# AM1027_POTS_REV01.net
KiCad netlist of a schematic drawn in EAGLE
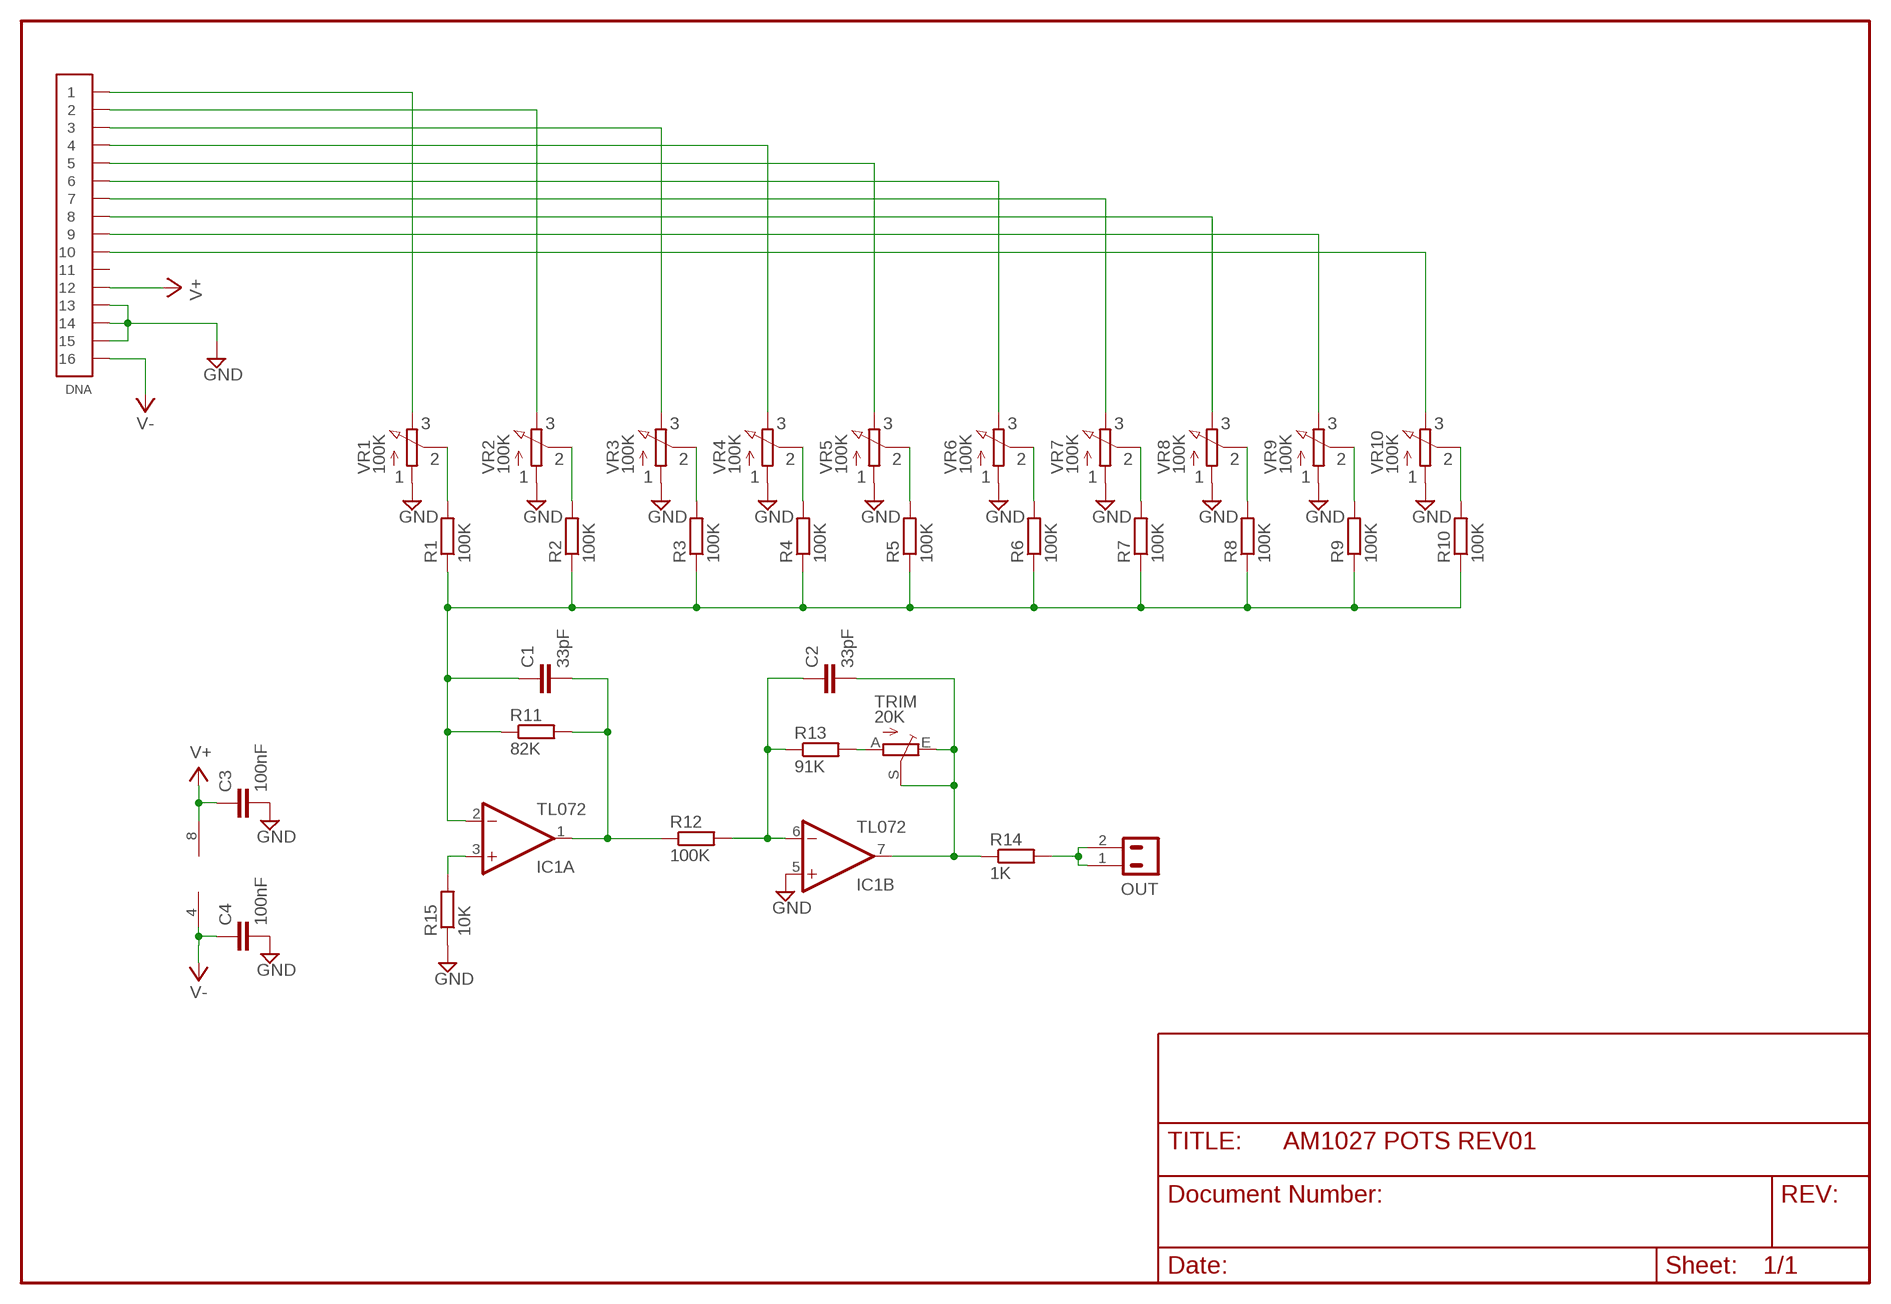
[diagram p0: schematic, sheet 1]

(export (version "E")
  (design (tool "Eeschema 10.0.6"))
  (components
    (comp (ref "C1")
      (value "33pF")
      (footprint "eagle-import:C050-025X075AM")
      (libsource (lib "eagle-import") (part "C-EU050-025X075AM"))
    )
    (comp (ref "C2")
      (value "33pF")
      (footprint "eagle-import:C050-025X075AM")
      (libsource (lib "eagle-import") (part "C-EU050-025X075AM"))
    )
    (comp (ref "C3")
      (value "100nF")
      (footprint "eagle-import:C050-025X075AM")
      (libsource (lib "eagle-import") (part "C-EU050-025X075AM"))
    )
    (comp (ref "C4")
      (value "100nF")
      (footprint "eagle-import:C050-025X075AM")
      (libsource (lib "eagle-import") (part "C-EU050-025X075AM"))
    )
    (comp (ref "DNA")
      (value "AMPWR16PIN")
      (footprint "eagle-import:AMPWR16")
      (libsource (lib "eagle-import") (part "AMPWR16PIN"))
    )
    (comp (ref "IC1")
      (value "TL072")
      (footprint "eagle-import:DIL08AM")
      (libsource (lib "eagle-import") (part "TL072"))
    )
    (comp (ref "OUT")
      (value "MA02-AM")
      (footprint "eagle-import:MA02-AM")
      (libsource (lib "eagle-import") (part "MA02-AM"))
    )
    (comp (ref "R1")
      (value "100K")
      (footprint "eagle-import:0207_10_AM")
      (libsource (lib "eagle-import") (part "R-EU_0207/10-AM"))
    )
    (comp (ref "R2")
      (value "100K")
      (footprint "eagle-import:0207_10_AM")
      (libsource (lib "eagle-import") (part "R-EU_0207/10-AM"))
    )
    (comp (ref "R3")
      (value "100K")
      (footprint "eagle-import:0207_10_AM")
      (libsource (lib "eagle-import") (part "R-EU_0207/10-AM"))
    )
    (comp (ref "R4")
      (value "100K")
      (footprint "eagle-import:0207_10_AM")
      (libsource (lib "eagle-import") (part "R-EU_0207/10-AM"))
    )
    (comp (ref "R5")
      (value "100K")
      (footprint "eagle-import:0207_10_AM")
      (libsource (lib "eagle-import") (part "R-EU_0207/10-AM"))
    )
    (comp (ref "R6")
      (value "100K")
      (footprint "eagle-import:0207_10_AM")
      (libsource (lib "eagle-import") (part "R-EU_0207/10-AM"))
    )
    (comp (ref "R7")
      (value "100K")
      (footprint "eagle-import:0207_10_AM")
      (libsource (lib "eagle-import") (part "R-EU_0207/10-AM"))
    )
    (comp (ref "R8")
      (value "100K")
      (footprint "eagle-import:0207_10_AM")
      (libsource (lib "eagle-import") (part "R-EU_0207/10-AM"))
    )
    (comp (ref "R9")
      (value "100K")
      (footprint "eagle-import:0207_10_AM")
      (libsource (lib "eagle-import") (part "R-EU_0207/10-AM"))
    )
    (comp (ref "R10")
      (value "100K")
      (footprint "eagle-import:0207_10_AM")
      (libsource (lib "eagle-import") (part "R-EU_0207/10-AM"))
    )
    (comp (ref "R11")
      (value "82K")
      (footprint "eagle-import:0207_10_AM")
      (libsource (lib "eagle-import") (part "R-EU_0207/10-AM"))
    )
    (comp (ref "R12")
      (value "100K")
      (footprint "eagle-import:0207_10_AM")
      (libsource (lib "eagle-import") (part "R-EU_0207/10-AM"))
    )
    (comp (ref "R13")
      (value "91K")
      (footprint "eagle-import:0207_10_AM")
      (libsource (lib "eagle-import") (part "R-EU_0207/10-AM"))
    )
    (comp (ref "R14")
      (value "1K")
      (footprint "eagle-import:0207_10_AM")
      (libsource (lib "eagle-import") (part "R-EU_0207/10-AM"))
    )
    (comp (ref "R15")
      (value "10K")
      (footprint "eagle-import:0207_10_AM")
      (libsource (lib "eagle-import") (part "R-EU_0207/10-AM"))
    )
    (comp (ref "TRIM")
      (value "20K")
      (footprint "eagle-import:S64W-AM")
      (libsource (lib "eagle-import") (part "TRIM_EU-S64W"))
    )
    (comp (ref "VR1")
      (value "100K")
      (footprint "eagle-import:SPECTROL148")
      (libsource (lib "eagle-import") (part "SPECTROL148"))
    )
    (comp (ref "VR2")
      (value "100K")
      (footprint "eagle-import:SPECTROL148")
      (libsource (lib "eagle-import") (part "SPECTROL148"))
    )
    (comp (ref "VR3")
      (value "100K")
      (footprint "eagle-import:SPECTROL148")
      (libsource (lib "eagle-import") (part "SPECTROL148"))
    )
    (comp (ref "VR4")
      (value "100K")
      (footprint "eagle-import:SPECTROL148")
      (libsource (lib "eagle-import") (part "SPECTROL148"))
    )
    (comp (ref "VR5")
      (value "100K")
      (footprint "eagle-import:SPECTROL148")
      (libsource (lib "eagle-import") (part "SPECTROL148"))
    )
    (comp (ref "VR6")
      (value "100K")
      (footprint "eagle-import:SPECTROL148")
      (libsource (lib "eagle-import") (part "SPECTROL148"))
    )
    (comp (ref "VR7")
      (value "100K")
      (footprint "eagle-import:SPECTROL148")
      (libsource (lib "eagle-import") (part "SPECTROL148"))
    )
    (comp (ref "VR8")
      (value "100K")
      (footprint "eagle-import:SPECTROL148")
      (libsource (lib "eagle-import") (part "SPECTROL148"))
    )
    (comp (ref "VR9")
      (value "100K")
      (footprint "eagle-import:SPECTROL148")
      (libsource (lib "eagle-import") (part "SPECTROL148"))
    )
    (comp (ref "VR10")
      (value "100K")
      (footprint "eagle-import:SPECTROL148")
      (libsource (lib "eagle-import") (part "SPECTROL148"))
    )
  )
  (nets
    (net (code "1") (name "GND") (class "Default")
      (node (ref "C3") (pin "P$4") (pinfunction "2_P$4") (pintype "passive"))
      (node (ref "C4") (pin "P$4") (pinfunction "2_P$4") (pintype "passive"))
      (node (ref "DNA") (pin "13") (pinfunction "13_13") (pintype "bidirectional"))
      (node (ref "DNA") (pin "14") (pinfunction "14_14") (pintype "bidirectional"))
      (node (ref "DNA") (pin "15") (pinfunction "15_15") (pintype "bidirectional"))
      (node (ref "IC1") (pin "5") (pinfunction "+IN_5") (pintype "input"))
      (node (ref "R15") (pin "P$1") (pinfunction "1_P$1") (pintype "passive"))
      (node (ref "VR1") (pin "P$1") (pinfunction "A_P$1") (pintype "passive"))
      (node (ref "VR10") (pin "P$1") (pinfunction "A_P$1") (pintype "passive"))
      (node (ref "VR2") (pin "P$1") (pinfunction "A_P$1") (pintype "passive"))
      (node (ref "VR3") (pin "P$1") (pinfunction "A_P$1") (pintype "passive"))
      (node (ref "VR4") (pin "P$1") (pinfunction "A_P$1") (pintype "passive"))
      (node (ref "VR5") (pin "P$1") (pinfunction "A_P$1") (pintype "passive"))
      (node (ref "VR6") (pin "P$1") (pinfunction "A_P$1") (pintype "passive"))
      (node (ref "VR7") (pin "P$1") (pinfunction "A_P$1") (pintype "passive"))
      (node (ref "VR8") (pin "P$1") (pinfunction "A_P$1") (pintype "passive"))
      (node (ref "VR9") (pin "P$1") (pinfunction "A_P$1") (pintype "passive"))
    )
    (net (code "2") (name "Net-(C1-1)") (class "Default")
      (node (ref "C1") (pin "P$3") (pinfunction "1_P$3") (pintype "passive"))
      (node (ref "IC1") (pin "2") (pinfunction "-IN_2") (pintype "input"))
      (node (ref "R1") (pin "P$1") (pinfunction "1_P$1") (pintype "passive"))
      (node (ref "R10") (pin "P$1") (pinfunction "1_P$1") (pintype "passive"))
      (node (ref "R11") (pin "P$1") (pinfunction "1_P$1") (pintype "passive"))
      (node (ref "R2") (pin "P$1") (pinfunction "1_P$1") (pintype "passive"))
      (node (ref "R3") (pin "P$1") (pinfunction "1_P$1") (pintype "passive"))
      (node (ref "R4") (pin "P$1") (pinfunction "1_P$1") (pintype "passive"))
      (node (ref "R5") (pin "P$1") (pinfunction "1_P$1") (pintype "passive"))
      (node (ref "R6") (pin "P$1") (pinfunction "1_P$1") (pintype "passive"))
      (node (ref "R7") (pin "P$1") (pinfunction "1_P$1") (pintype "passive"))
      (node (ref "R8") (pin "P$1") (pinfunction "1_P$1") (pintype "passive"))
      (node (ref "R9") (pin "P$1") (pinfunction "1_P$1") (pintype "passive"))
    )
    (net (code "3") (name "Net-(C1-2)") (class "Default")
      (node (ref "C1") (pin "P$4") (pinfunction "2_P$4") (pintype "passive"))
      (node (ref "IC1") (pin "1") (pinfunction "OUT_1") (pintype "output"))
      (node (ref "R11") (pin "P$2") (pinfunction "2_P$2") (pintype "passive"))
      (node (ref "R12") (pin "P$1") (pinfunction "1_P$1") (pintype "passive"))
    )
    (net (code "4") (name "Net-(C2-1)") (class "Default")
      (node (ref "C2") (pin "P$3") (pinfunction "1_P$3") (pintype "passive"))
      (node (ref "IC1") (pin "6") (pinfunction "-IN_6") (pintype "input"))
      (node (ref "R12") (pin "P$2") (pinfunction "2_P$2") (pintype "passive"))
      (node (ref "R13") (pin "P$1") (pinfunction "1_P$1") (pintype "passive"))
    )
    (net (code "5") (name "Net-(C2-2)") (class "Default")
      (node (ref "C2") (pin "P$4") (pinfunction "2_P$4") (pintype "passive"))
      (node (ref "IC1") (pin "7") (pinfunction "OUT_7") (pintype "output"))
      (node (ref "R14") (pin "P$1") (pinfunction "1_P$1") (pintype "passive"))
      (node (ref "TRIM") (pin "E") (pinfunction "E_E") (pintype "passive"))
      (node (ref "TRIM") (pin "S") (pinfunction "S_S") (pintype "passive"))
    )
    (net (code "6") (name "Net-(IC1A-+IN)") (class "Default")
      (node (ref "IC1") (pin "3") (pinfunction "+IN_3") (pintype "input"))
      (node (ref "R15") (pin "P$2") (pinfunction "2_P$2") (pintype "passive"))
    )
    (net (code "7") (name "Net-(OUT-P$1)") (class "Default")
      (node (ref "OUT") (pin "1") (pinfunction "P$1_1") (pintype "passive"))
      (node (ref "OUT") (pin "2") (pinfunction "P$2_2") (pintype "passive"))
      (node (ref "R14") (pin "P$2") (pinfunction "2_P$2") (pintype "passive"))
    )
    (net (code "8") (name "Net-(R1-2)") (class "Default")
      (node (ref "R1") (pin "P$2") (pinfunction "2_P$2") (pintype "passive"))
      (node (ref "VR1") (pin "P$2") (pinfunction "S_P$2") (pintype "passive"))
    )
    (net (code "9") (name "Net-(R2-2)") (class "Default")
      (node (ref "R2") (pin "P$2") (pinfunction "2_P$2") (pintype "passive"))
      (node (ref "VR2") (pin "P$2") (pinfunction "S_P$2") (pintype "passive"))
    )
    (net (code "10") (name "Net-(R3-2)") (class "Default")
      (node (ref "R3") (pin "P$2") (pinfunction "2_P$2") (pintype "passive"))
      (node (ref "VR3") (pin "P$2") (pinfunction "S_P$2") (pintype "passive"))
    )
    (net (code "11") (name "Net-(R4-2)") (class "Default")
      (node (ref "R4") (pin "P$2") (pinfunction "2_P$2") (pintype "passive"))
      (node (ref "VR4") (pin "P$2") (pinfunction "S_P$2") (pintype "passive"))
    )
    (net (code "12") (name "Net-(R5-2)") (class "Default")
      (node (ref "R5") (pin "P$2") (pinfunction "2_P$2") (pintype "passive"))
      (node (ref "VR5") (pin "P$2") (pinfunction "S_P$2") (pintype "passive"))
    )
    (net (code "13") (name "Net-(R6-2)") (class "Default")
      (node (ref "R6") (pin "P$2") (pinfunction "2_P$2") (pintype "passive"))
      (node (ref "VR6") (pin "P$2") (pinfunction "S_P$2") (pintype "passive"))
    )
    (net (code "14") (name "Net-(R7-2)") (class "Default")
      (node (ref "R7") (pin "P$2") (pinfunction "2_P$2") (pintype "passive"))
      (node (ref "VR7") (pin "P$2") (pinfunction "S_P$2") (pintype "passive"))
    )
    (net (code "15") (name "Net-(R8-2)") (class "Default")
      (node (ref "R8") (pin "P$2") (pinfunction "2_P$2") (pintype "passive"))
      (node (ref "VR8") (pin "P$2") (pinfunction "S_P$2") (pintype "passive"))
    )
    (net (code "16") (name "Net-(R9-2)") (class "Default")
      (node (ref "R9") (pin "P$2") (pinfunction "2_P$2") (pintype "passive"))
      (node (ref "VR9") (pin "P$2") (pinfunction "S_P$2") (pintype "passive"))
    )
    (net (code "17") (name "Net-(R10-2)") (class "Default")
      (node (ref "R10") (pin "P$2") (pinfunction "2_P$2") (pintype "passive"))
      (node (ref "VR10") (pin "P$2") (pinfunction "S_P$2") (pintype "passive"))
    )
    (net (code "18") (name "Net-(R13-2)") (class "Default")
      (node (ref "R13") (pin "P$2") (pinfunction "2_P$2") (pintype "passive"))
      (node (ref "TRIM") (pin "A") (pinfunction "A_A") (pintype "passive"))
    )
    (net (code "19") (name "Net-(VR1-E)") (class "Default")
      (node (ref "DNA") (pin "1") (pinfunction "1_1") (pintype "bidirectional"))
      (node (ref "VR1") (pin "P$3") (pinfunction "E_P$3") (pintype "passive"))
    )
    (net (code "20") (name "Net-(VR2-E)") (class "Default")
      (node (ref "DNA") (pin "2") (pinfunction "2_2") (pintype "bidirectional"))
      (node (ref "VR2") (pin "P$3") (pinfunction "E_P$3") (pintype "passive"))
    )
    (net (code "21") (name "Net-(VR3-E)") (class "Default")
      (node (ref "DNA") (pin "3") (pinfunction "3_3") (pintype "bidirectional"))
      (node (ref "VR3") (pin "P$3") (pinfunction "E_P$3") (pintype "passive"))
    )
    (net (code "22") (name "Net-(VR4-E)") (class "Default")
      (node (ref "DNA") (pin "4") (pinfunction "4_4") (pintype "bidirectional"))
      (node (ref "VR4") (pin "P$3") (pinfunction "E_P$3") (pintype "passive"))
    )
    (net (code "23") (name "Net-(VR5-E)") (class "Default")
      (node (ref "DNA") (pin "5") (pinfunction "5_5") (pintype "bidirectional"))
      (node (ref "VR5") (pin "P$3") (pinfunction "E_P$3") (pintype "passive"))
    )
    (net (code "24") (name "Net-(VR6-E)") (class "Default")
      (node (ref "DNA") (pin "6") (pinfunction "6_6") (pintype "bidirectional"))
      (node (ref "VR6") (pin "P$3") (pinfunction "E_P$3") (pintype "passive"))
    )
    (net (code "25") (name "Net-(VR7-E)") (class "Default")
      (node (ref "DNA") (pin "7") (pinfunction "7_7") (pintype "bidirectional"))
      (node (ref "VR7") (pin "P$3") (pinfunction "E_P$3") (pintype "passive"))
    )
    (net (code "26") (name "Net-(VR8-E)") (class "Default")
      (node (ref "DNA") (pin "8") (pinfunction "8_8") (pintype "bidirectional"))
      (node (ref "VR8") (pin "P$3") (pinfunction "E_P$3") (pintype "passive"))
    )
    (net (code "27") (name "Net-(VR9-E)") (class "Default")
      (node (ref "DNA") (pin "9") (pinfunction "9_9") (pintype "bidirectional"))
      (node (ref "VR9") (pin "P$3") (pinfunction "E_P$3") (pintype "passive"))
    )
    (net (code "28") (name "Net-(VR10-E)") (class "Default")
      (node (ref "DNA") (pin "10") (pinfunction "10_10") (pintype "bidirectional"))
      (node (ref "VR10") (pin "P$3") (pinfunction "E_P$3") (pintype "passive"))
    )
    (net (code "29") (name "V+") (class "Default")
      (node (ref "C3") (pin "P$3") (pinfunction "1_P$3") (pintype "passive"))
      (node (ref "DNA") (pin "12") (pinfunction "12_12") (pintype "bidirectional"))
      (node (ref "IC1") (pin "8") (pinfunction "V+_8") (pintype "power_in"))
    )
    (net (code "30") (name "V-") (class "Default")
      (node (ref "C4") (pin "P$3") (pinfunction "1_P$3") (pintype "passive"))
      (node (ref "DNA") (pin "16") (pinfunction "16_16") (pintype "bidirectional"))
      (node (ref "IC1") (pin "4") (pinfunction "V-_4") (pintype "power_in"))
    )
    (net (code "31") (name "unconnected-(DNA-Pad11)") (class "Default")
      (node (ref "DNA") (pin "11") (pinfunction "11_11") (pintype "bidirectional"))
    )
  )
)
